# droidbot_main_HW.net
KiCad netlist of a schematic drawn in EAGLE
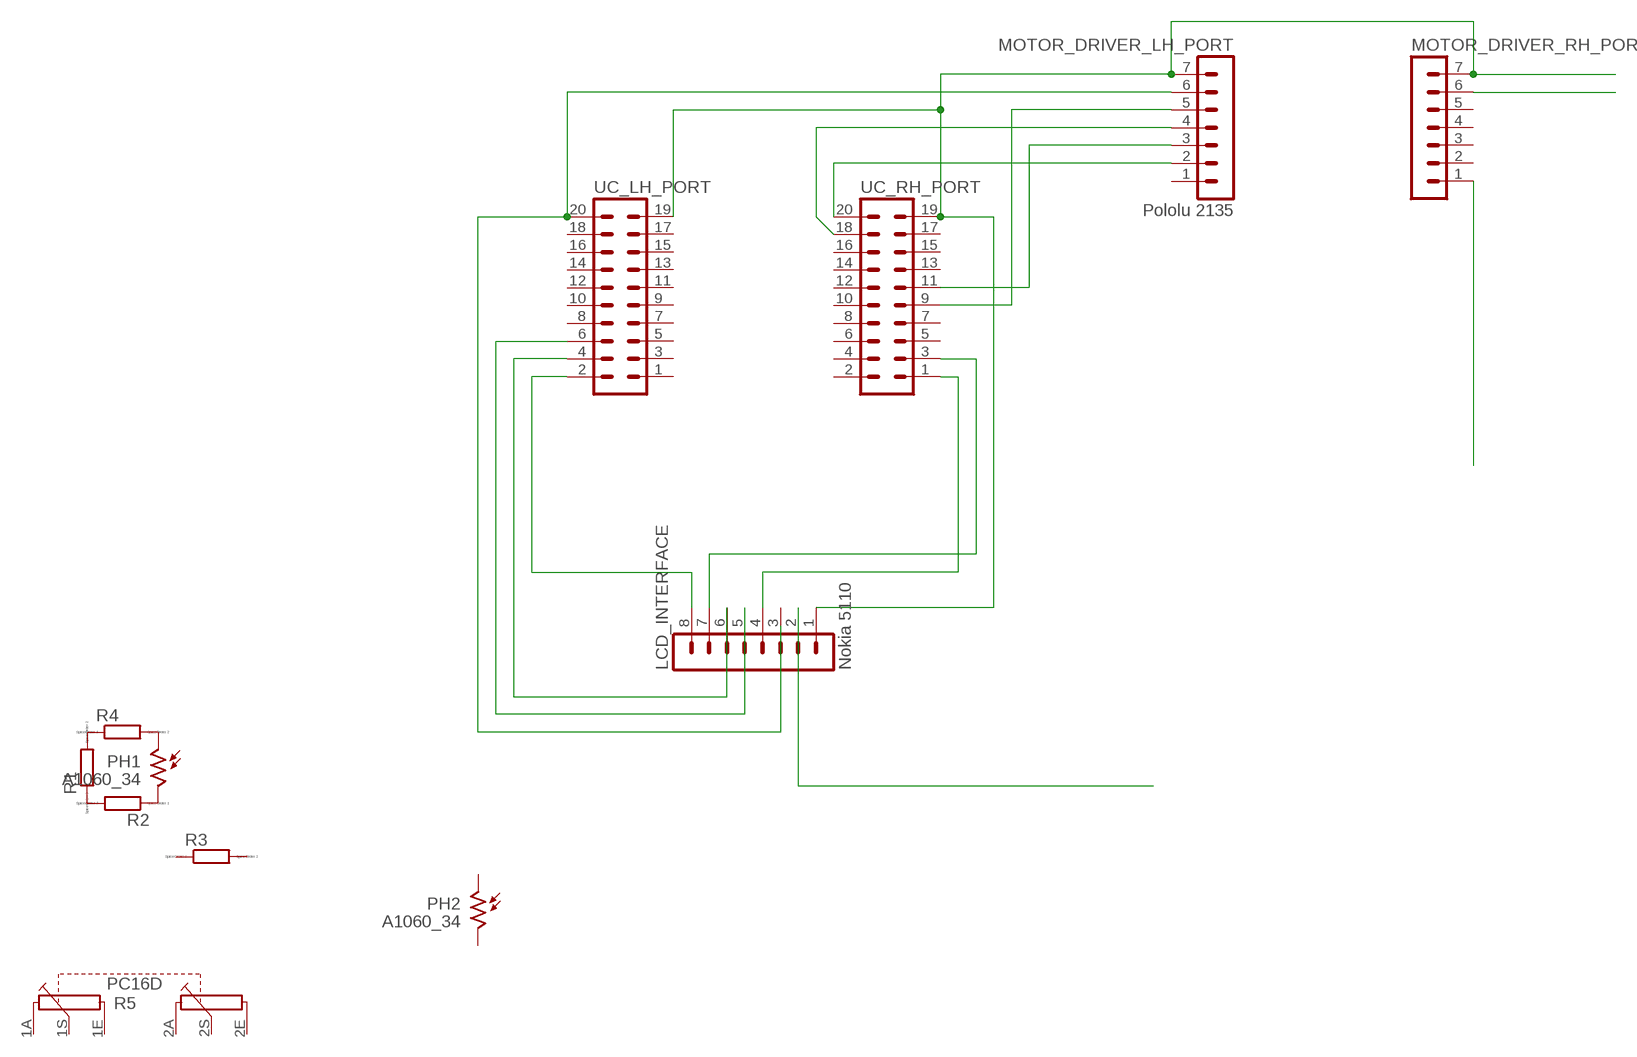
[diagram p0: schematic, sheet 1]

(export (version "E")
  (design (tool "Eeschema 10.0.6"))
  (components
    (comp (ref "LCD_INTERFACE")
      (value "Nokia 5110")
      (footprint "eagle-import:MA08-1")
      (libsource (lib "eagle-import") (part "MA08-1"))
    )
    (comp (ref "MOTOR_DRIVER_LH_PORT")
      (value "Pololu 2135")
      (footprint "eagle-import:MA07-1")
      (libsource (lib "eagle-import") (part "MA07-1"))
    )
    (comp (ref "MOTOR_DRIVER_RH_PORT")
      (value "MA07-1")
      (footprint "eagle-import:MA07-1")
      (libsource (lib "eagle-import") (part "MA07-1"))
    )
    (comp (ref "PH1")
      (value "A1060_34")
      (footprint "eagle-import:T0-46-A10XX")
      (libsource (lib "eagle-import") (part "A1060_34"))
    )
    (comp (ref "PH2")
      (value "A1060_34")
      (footprint "eagle-import:T0-46-A10XX")
      (libsource (lib "eagle-import") (part "A1060_34"))
    )
    (comp (ref "R1")
      (value "R0204/7")
      (footprint "eagle-import:0204_7")
      (libsource (lib "eagle-import") (part "R0204/7"))
    )
    (comp (ref "R2")
      (value "R0204/7")
      (footprint "eagle-import:0204_7")
      (libsource (lib "eagle-import") (part "R0204/7"))
    )
    (comp (ref "R3")
      (value "R0204/7")
      (footprint "eagle-import:0204_7")
      (libsource (lib "eagle-import") (part "R0204/7"))
    )
    (comp (ref "R4")
      (value "R0204/7")
      (footprint "eagle-import:0204_7")
      (libsource (lib "eagle-import") (part "R0204/7"))
    )
    (comp (ref "R5")
      (value "PC16D")
      (footprint "eagle-import:PC16D")
      (libsource (lib "eagle-import") (part "PC16D"))
    )
    (comp (ref "UC_LH_PORT")
      (value "MA10-2")
      (footprint "eagle-import:MA10-2")
      (libsource (lib "eagle-import") (part "MA10-2"))
    )
    (comp (ref "UC_RH_PORT")
      (value "MA10-2")
      (footprint "eagle-import:MA10-2")
      (libsource (lib "eagle-import") (part "MA10-2"))
    )
  )
  (nets
    (net (code "1") (name "Net-(LCD_INTERFACE-Pad1)") (class "Default")
      (node (ref "LCD_INTERFACE") (pin "1") (pinfunction "1_1") (pintype "passive"))
      (node (ref "MOTOR_DRIVER_LH_PORT") (pin "7") (pinfunction "7_7") (pintype "passive"))
      (node (ref "MOTOR_DRIVER_RH_PORT") (pin "7") (pinfunction "7_7") (pintype "passive"))
      (node (ref "UC_LH_PORT") (pin "19") (pinfunction "19_19") (pintype "passive"))
      (node (ref "UC_RH_PORT") (pin "19") (pinfunction "19_19") (pintype "passive"))
    )
    (net (code "2") (name "Net-(LCD_INTERFACE-Pad4)") (class "Default")
      (node (ref "LCD_INTERFACE") (pin "4") (pinfunction "4_4") (pintype "passive"))
      (node (ref "UC_RH_PORT") (pin "1") (pinfunction "1_1") (pintype "passive"))
    )
    (net (code "3") (name "Net-(LCD_INTERFACE-Pad5)") (class "Default")
      (node (ref "LCD_INTERFACE") (pin "5") (pinfunction "5_5") (pintype "passive"))
      (node (ref "UC_LH_PORT") (pin "6") (pinfunction "6_6") (pintype "passive"))
    )
    (net (code "4") (name "Net-(LCD_INTERFACE-Pad6)") (class "Default")
      (node (ref "LCD_INTERFACE") (pin "6") (pinfunction "6_6") (pintype "passive"))
      (node (ref "UC_LH_PORT") (pin "4") (pinfunction "4_4") (pintype "passive"))
    )
    (net (code "5") (name "Net-(LCD_INTERFACE-Pad7)") (class "Default")
      (node (ref "LCD_INTERFACE") (pin "7") (pinfunction "7_7") (pintype "passive"))
      (node (ref "UC_RH_PORT") (pin "3") (pinfunction "3_3") (pintype "passive"))
    )
    (net (code "6") (name "Net-(LCD_INTERFACE-Pad8)") (class "Default")
      (node (ref "LCD_INTERFACE") (pin "8") (pinfunction "8_8") (pintype "passive"))
      (node (ref "UC_LH_PORT") (pin "2") (pinfunction "2_2") (pintype "passive"))
    )
    (net (code "7") (name "Net-(MOTOR_DRIVER_LH_PORT-Pad2)") (class "Default")
      (node (ref "MOTOR_DRIVER_LH_PORT") (pin "2") (pinfunction "2_2") (pintype "passive"))
      (node (ref "UC_RH_PORT") (pin "20") (pinfunction "20_20") (pintype "passive"))
    )
    (net (code "8") (name "Net-(MOTOR_DRIVER_LH_PORT-Pad3)") (class "Default")
      (node (ref "MOTOR_DRIVER_LH_PORT") (pin "3") (pinfunction "3_3") (pintype "passive"))
      (node (ref "UC_RH_PORT") (pin "11") (pinfunction "11_11") (pintype "passive"))
    )
    (net (code "9") (name "Net-(MOTOR_DRIVER_LH_PORT-Pad4)") (class "Default")
      (node (ref "MOTOR_DRIVER_LH_PORT") (pin "4") (pinfunction "4_4") (pintype "passive"))
      (node (ref "UC_RH_PORT") (pin "18") (pinfunction "18_18") (pintype "passive"))
    )
    (net (code "10") (name "Net-(MOTOR_DRIVER_LH_PORT-Pad5)") (class "Default")
      (node (ref "MOTOR_DRIVER_LH_PORT") (pin "5") (pinfunction "5_5") (pintype "passive"))
      (node (ref "UC_RH_PORT") (pin "9") (pinfunction "9_9") (pintype "passive"))
    )
    (net (code "11") (name "Net-(MOTOR_DRIVER_LH_PORT-Pad6)") (class "Default")
      (node (ref "MOTOR_DRIVER_LH_PORT") (pin "6") (pinfunction "6_6") (pintype "passive"))
      (node (ref "UC_LH_PORT") (pin "20") (pinfunction "20_20") (pintype "passive"))
    )
    (net (code "12") (name "Net-(PH1-Pad1)") (class "Default")
      (node (ref "PH1") (pin "1") (pinfunction "1_1") (pintype "passive"))
      (node (ref "R4") (pin "2") (pinfunction "2_2") (pintype "passive"))
    )
    (net (code "13") (name "Net-(PH1-Pad2)") (class "Default")
      (node (ref "PH1") (pin "2") (pinfunction "2_2") (pintype "passive"))
      (node (ref "R2") (pin "1") (pinfunction "1_1") (pintype "passive"))
    )
    (net (code "14") (name "Net-(R1-Pad1)") (class "Default")
      (node (ref "R1") (pin "1") (pinfunction "1_1") (pintype "passive"))
      (node (ref "R2") (pin "2") (pinfunction "2_2") (pintype "passive"))
    )
    (net (code "15") (name "Net-(R1-Pad2)") (class "Default")
      (node (ref "R1") (pin "2") (pinfunction "2_2") (pintype "passive"))
      (node (ref "R4") (pin "1") (pinfunction "1_1") (pintype "passive"))
    )
    (net (code "16") (name "unconnected-(LCD_INTERFACE-Pad2)") (class "Default")
      (node (ref "LCD_INTERFACE") (pin "2") (pinfunction "2_2") (pintype "passive"))
    )
    (net (code "17") (name "unconnected-(LCD_INTERFACE-Pad3)") (class "Default")
      (node (ref "LCD_INTERFACE") (pin "3") (pinfunction "3_3") (pintype "passive"))
    )
    (net (code "18") (name "unconnected-(MOTOR_DRIVER_LH_PORT-Pad1)") (class "Default")
      (node (ref "MOTOR_DRIVER_LH_PORT") (pin "1") (pinfunction "1_1") (pintype "passive"))
    )
    (net (code "19") (name "unconnected-(MOTOR_DRIVER_RH_PORT-Pad1)") (class "Default")
      (node (ref "MOTOR_DRIVER_RH_PORT") (pin "1") (pinfunction "1_1") (pintype "passive"))
    )
    (net (code "20") (name "unconnected-(MOTOR_DRIVER_RH_PORT-Pad2)") (class "Default")
      (node (ref "MOTOR_DRIVER_RH_PORT") (pin "2") (pinfunction "2_2") (pintype "passive"))
    )
    (net (code "21") (name "unconnected-(MOTOR_DRIVER_RH_PORT-Pad3)") (class "Default")
      (node (ref "MOTOR_DRIVER_RH_PORT") (pin "3") (pinfunction "3_3") (pintype "passive"))
    )
    (net (code "22") (name "unconnected-(MOTOR_DRIVER_RH_PORT-Pad4)") (class "Default")
      (node (ref "MOTOR_DRIVER_RH_PORT") (pin "4") (pinfunction "4_4") (pintype "passive"))
    )
    (net (code "23") (name "unconnected-(MOTOR_DRIVER_RH_PORT-Pad5)") (class "Default")
      (node (ref "MOTOR_DRIVER_RH_PORT") (pin "5") (pinfunction "5_5") (pintype "passive"))
    )
    (net (code "24") (name "unconnected-(MOTOR_DRIVER_RH_PORT-Pad6)") (class "Default")
      (node (ref "MOTOR_DRIVER_RH_PORT") (pin "6") (pinfunction "6_6") (pintype "passive"))
    )
    (net (code "25") (name "unconnected-(PH2-Pad1)") (class "Default")
      (node (ref "PH2") (pin "1") (pinfunction "1_1") (pintype "passive"))
    )
    (net (code "26") (name "unconnected-(PH2-Pad2)") (class "Default")
      (node (ref "PH2") (pin "2") (pinfunction "2_2") (pintype "passive"))
    )
    (net (code "27") (name "unconnected-(R3-Pad1)") (class "Default")
      (node (ref "R3") (pin "1") (pinfunction "1_1") (pintype "passive"))
    )
    (net (code "28") (name "unconnected-(R3-Pad2)") (class "Default")
      (node (ref "R3") (pin "2") (pinfunction "2_2") (pintype "passive"))
    )
    (net (code "29") (name "unconnected-(R5-Pad1A)") (class "Default")
      (node (ref "R5") (pin "1A") (pinfunction "1A_1A") (pintype "passive"))
    )
    (net (code "30") (name "unconnected-(R5-Pad1E)") (class "Default")
      (node (ref "R5") (pin "1E") (pinfunction "1E_1E") (pintype "passive"))
    )
    (net (code "31") (name "unconnected-(R5-Pad1S)") (class "Default")
      (node (ref "R5") (pin "1S") (pinfunction "1S_1S") (pintype "passive"))
    )
    (net (code "32") (name "unconnected-(R5-Pad2A)") (class "Default")
      (node (ref "R5") (pin "2A") (pinfunction "2A_2A") (pintype "passive"))
    )
    (net (code "33") (name "unconnected-(R5-Pad2E)") (class "Default")
      (node (ref "R5") (pin "2E") (pinfunction "2E_2E") (pintype "passive"))
    )
    (net (code "34") (name "unconnected-(R5-Pad2S)") (class "Default")
      (node (ref "R5") (pin "2S") (pinfunction "2S_2S") (pintype "passive"))
    )
    (net (code "35") (name "unconnected-(UC_LH_PORT-Pad1)") (class "Default")
      (node (ref "UC_LH_PORT") (pin "1") (pinfunction "1_1") (pintype "passive"))
    )
    (net (code "36") (name "unconnected-(UC_LH_PORT-Pad3)") (class "Default")
      (node (ref "UC_LH_PORT") (pin "3") (pinfunction "3_3") (pintype "passive"))
    )
    (net (code "37") (name "unconnected-(UC_LH_PORT-Pad5)") (class "Default")
      (node (ref "UC_LH_PORT") (pin "5") (pinfunction "5_5") (pintype "passive"))
    )
    (net (code "38") (name "unconnected-(UC_LH_PORT-Pad7)") (class "Default")
      (node (ref "UC_LH_PORT") (pin "7") (pinfunction "7_7") (pintype "passive"))
    )
    (net (code "39") (name "unconnected-(UC_LH_PORT-Pad8)") (class "Default")
      (node (ref "UC_LH_PORT") (pin "8") (pinfunction "8_8") (pintype "passive"))
    )
    (net (code "40") (name "unconnected-(UC_LH_PORT-Pad9)") (class "Default")
      (node (ref "UC_LH_PORT") (pin "9") (pinfunction "9_9") (pintype "passive"))
    )
    (net (code "41") (name "unconnected-(UC_LH_PORT-Pad10)") (class "Default")
      (node (ref "UC_LH_PORT") (pin "10") (pinfunction "10_10") (pintype "passive"))
    )
    (net (code "42") (name "unconnected-(UC_LH_PORT-Pad11)") (class "Default")
      (node (ref "UC_LH_PORT") (pin "11") (pinfunction "11_11") (pintype "passive"))
    )
    (net (code "43") (name "unconnected-(UC_LH_PORT-Pad12)") (class "Default")
      (node (ref "UC_LH_PORT") (pin "12") (pinfunction "12_12") (pintype "passive"))
    )
    (net (code "44") (name "unconnected-(UC_LH_PORT-Pad13)") (class "Default")
      (node (ref "UC_LH_PORT") (pin "13") (pinfunction "13_13") (pintype "passive"))
    )
    (net (code "45") (name "unconnected-(UC_LH_PORT-Pad14)") (class "Default")
      (node (ref "UC_LH_PORT") (pin "14") (pinfunction "14_14") (pintype "passive"))
    )
    (net (code "46") (name "unconnected-(UC_LH_PORT-Pad15)") (class "Default")
      (node (ref "UC_LH_PORT") (pin "15") (pinfunction "15_15") (pintype "passive"))
    )
    (net (code "47") (name "unconnected-(UC_LH_PORT-Pad16)") (class "Default")
      (node (ref "UC_LH_PORT") (pin "16") (pinfunction "16_16") (pintype "passive"))
    )
    (net (code "48") (name "unconnected-(UC_LH_PORT-Pad17)") (class "Default")
      (node (ref "UC_LH_PORT") (pin "17") (pinfunction "17_17") (pintype "passive"))
    )
    (net (code "49") (name "unconnected-(UC_LH_PORT-Pad18)") (class "Default")
      (node (ref "UC_LH_PORT") (pin "18") (pinfunction "18_18") (pintype "passive"))
    )
    (net (code "50") (name "unconnected-(UC_RH_PORT-Pad2)") (class "Default")
      (node (ref "UC_RH_PORT") (pin "2") (pinfunction "2_2") (pintype "passive"))
    )
    (net (code "51") (name "unconnected-(UC_RH_PORT-Pad4)") (class "Default")
      (node (ref "UC_RH_PORT") (pin "4") (pinfunction "4_4") (pintype "passive"))
    )
    (net (code "52") (name "unconnected-(UC_RH_PORT-Pad5)") (class "Default")
      (node (ref "UC_RH_PORT") (pin "5") (pinfunction "5_5") (pintype "passive"))
    )
    (net (code "53") (name "unconnected-(UC_RH_PORT-Pad6)") (class "Default")
      (node (ref "UC_RH_PORT") (pin "6") (pinfunction "6_6") (pintype "passive"))
    )
    (net (code "54") (name "unconnected-(UC_RH_PORT-Pad7)") (class "Default")
      (node (ref "UC_RH_PORT") (pin "7") (pinfunction "7_7") (pintype "passive"))
    )
    (net (code "55") (name "unconnected-(UC_RH_PORT-Pad8)") (class "Default")
      (node (ref "UC_RH_PORT") (pin "8") (pinfunction "8_8") (pintype "passive"))
    )
    (net (code "56") (name "unconnected-(UC_RH_PORT-Pad10)") (class "Default")
      (node (ref "UC_RH_PORT") (pin "10") (pinfunction "10_10") (pintype "passive"))
    )
    (net (code "57") (name "unconnected-(UC_RH_PORT-Pad12)") (class "Default")
      (node (ref "UC_RH_PORT") (pin "12") (pinfunction "12_12") (pintype "passive"))
    )
    (net (code "58") (name "unconnected-(UC_RH_PORT-Pad13)") (class "Default")
      (node (ref "UC_RH_PORT") (pin "13") (pinfunction "13_13") (pintype "passive"))
    )
    (net (code "59") (name "unconnected-(UC_RH_PORT-Pad14)") (class "Default")
      (node (ref "UC_RH_PORT") (pin "14") (pinfunction "14_14") (pintype "passive"))
    )
    (net (code "60") (name "unconnected-(UC_RH_PORT-Pad15)") (class "Default")
      (node (ref "UC_RH_PORT") (pin "15") (pinfunction "15_15") (pintype "passive"))
    )
    (net (code "61") (name "unconnected-(UC_RH_PORT-Pad16)") (class "Default")
      (node (ref "UC_RH_PORT") (pin "16") (pinfunction "16_16") (pintype "passive"))
    )
    (net (code "62") (name "unconnected-(UC_RH_PORT-Pad17)") (class "Default")
      (node (ref "UC_RH_PORT") (pin "17") (pinfunction "17_17") (pintype "passive"))
    )
  )
)
